# paper_tape.net
KiCad netlist of a schematic drawn in EAGLE
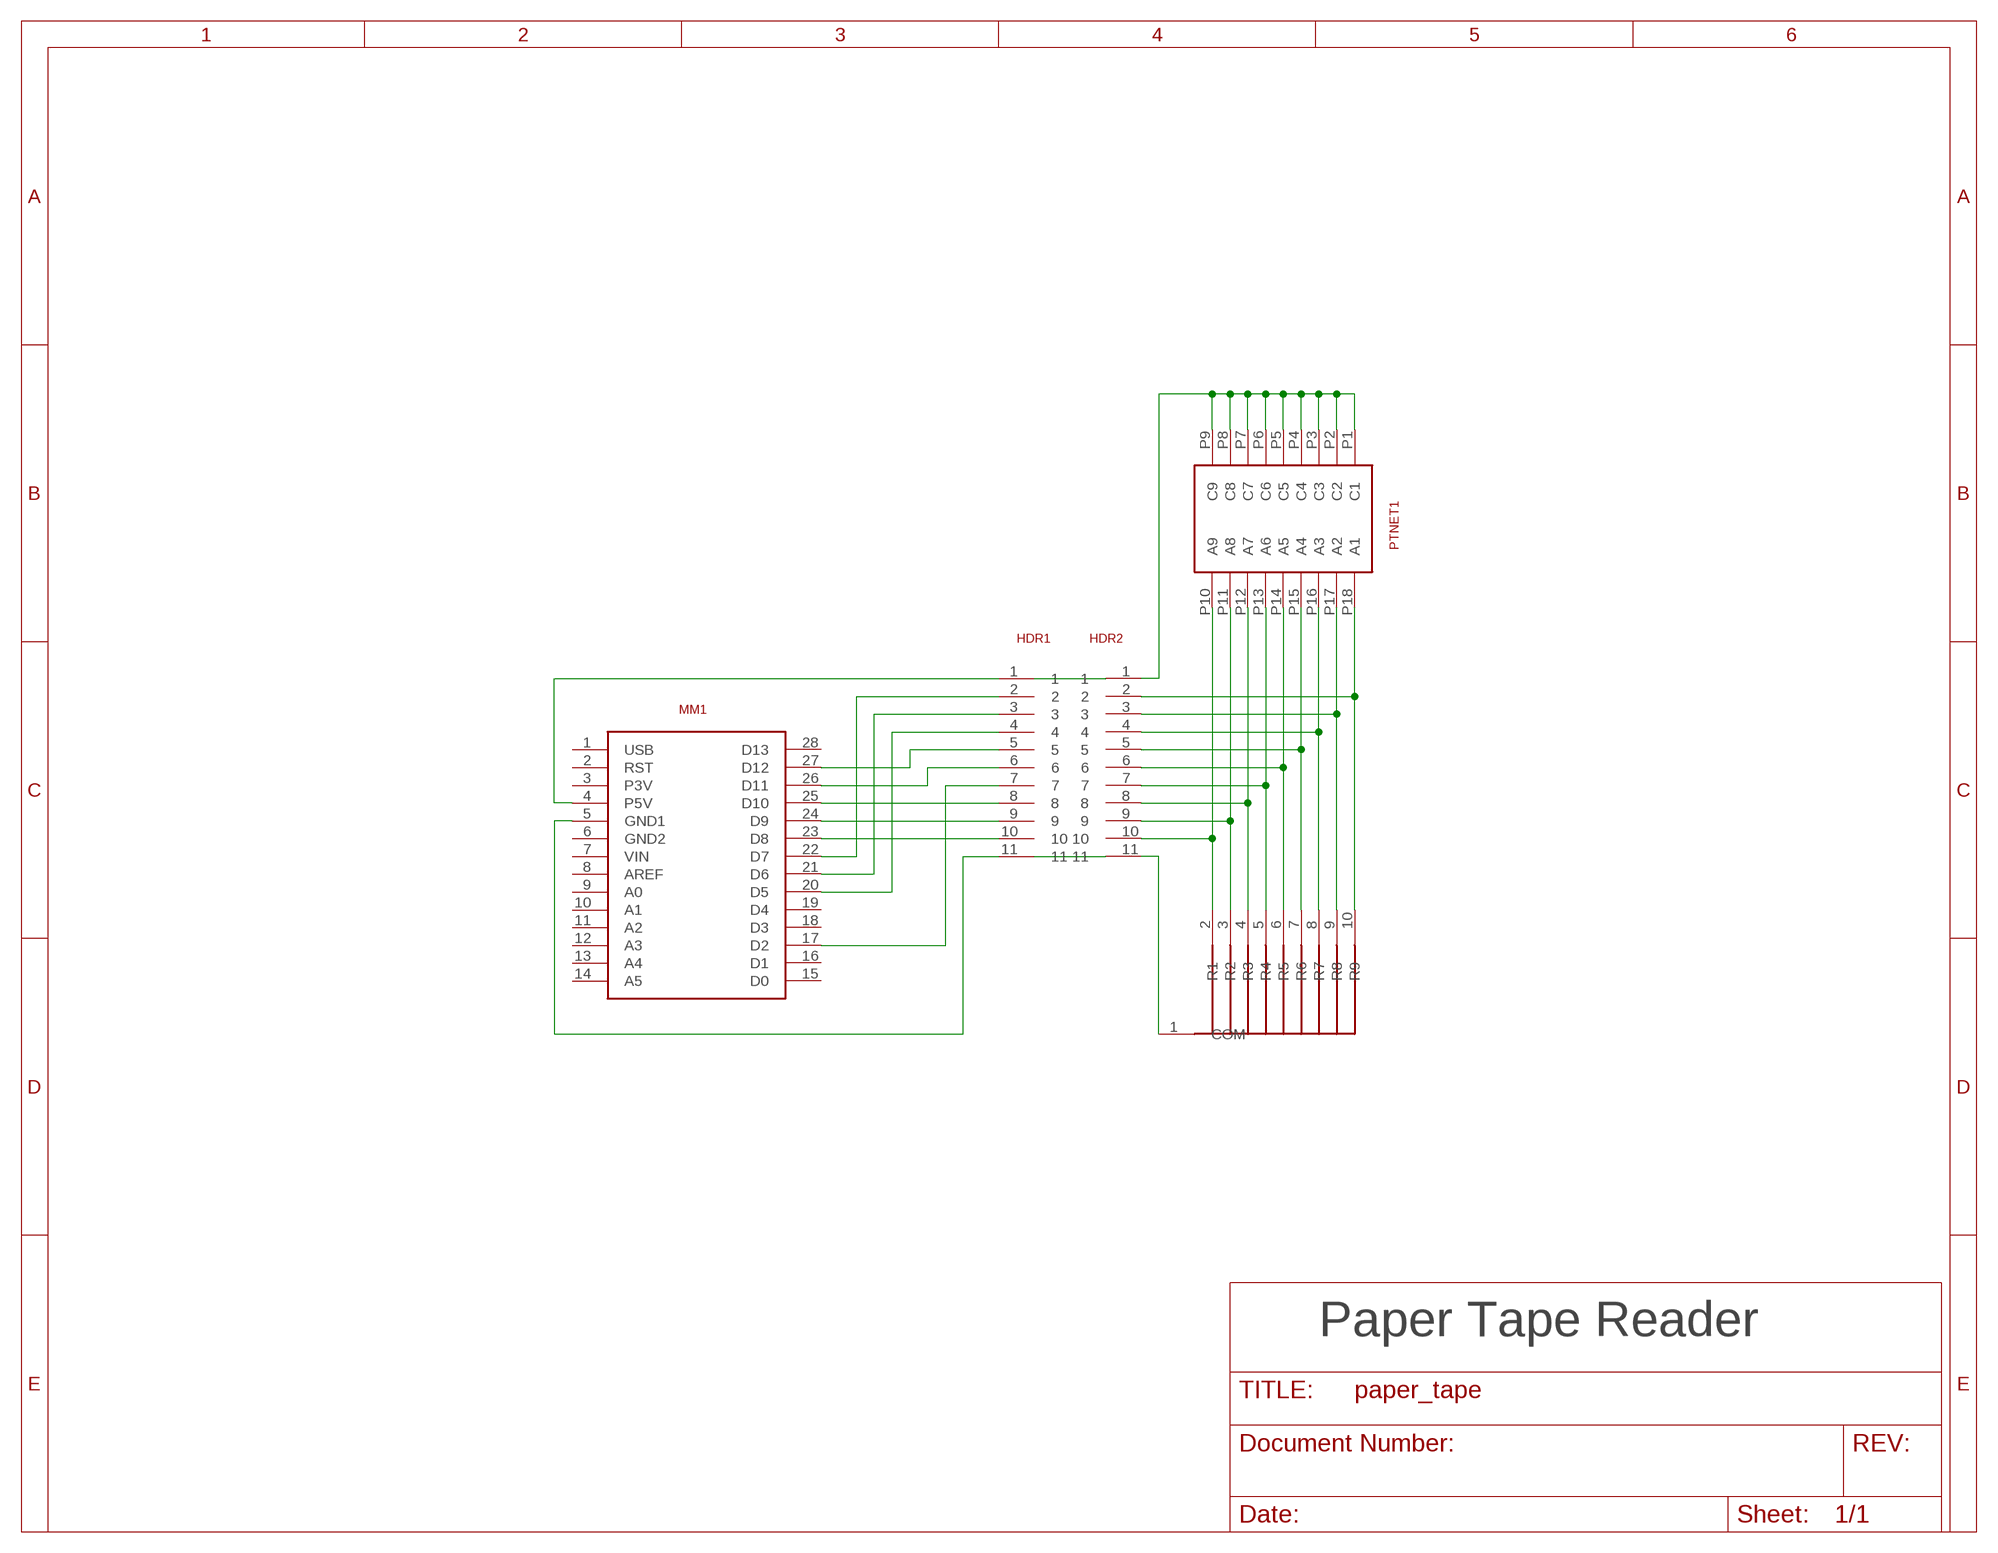
[diagram p0: schematic, sheet 1]

(export (version "E")
  (design (tool "Eeschema 10.0.6"))
  (components
    (comp (ref "HDR1")
      (value "HEADER")
      (footprint "eagle-import:SIP11")
      (libsource (lib "eagle-import") (part "HEADER"))
    )
    (comp (ref "HDR2")
      (value "HEADER")
      (footprint "eagle-import:SIP11")
      (libsource (lib "eagle-import") (part "HEADER"))
    )
    (comp (ref "MM1")
      (value "METRO_MINI")
      (footprint "eagle-import:DIP28")
      (libsource (lib "eagle-import") (part "METRO_MINI"))
    )
    (comp (ref "PTNET1")
      (value "PBX89")
      (footprint "eagle-import:DIP18N")
      (libsource (lib "eagle-import") (part "PBX89"))
    )
    (comp (ref "RN1")
      (value "1k")
      (footprint "eagle-import:SIP10")
      (libsource (lib "eagle-import") (part "RNET"))
    )
  )
  (nets
    (net (code "1") (name "/GND") (class "Default")
      (node (ref "HDR1") (pin "11") (pinfunction "11_11") (pintype "bidirectional"))
      (node (ref "HDR2") (pin "11") (pinfunction "11_11") (pintype "bidirectional"))
      (node (ref "MM1") (pin "5") (pinfunction "GND1_5") (pintype "bidirectional"))
      (node (ref "RN1") (pin "1") (pinfunction "COM_1") (pintype "bidirectional"))
    )
    (net (code "2") (name "/P5V") (class "Default")
      (node (ref "HDR2") (pin "1") (pinfunction "1_1") (pintype "bidirectional"))
      (node (ref "PTNET1") (pin "P1") (pinfunction "C1_P1") (pintype "bidirectional"))
      (node (ref "PTNET1") (pin "P2") (pinfunction "C2_P2") (pintype "bidirectional"))
      (node (ref "PTNET1") (pin "P3") (pinfunction "C3_P3") (pintype "bidirectional"))
      (node (ref "PTNET1") (pin "P4") (pinfunction "C4_P4") (pintype "bidirectional"))
      (node (ref "PTNET1") (pin "P5") (pinfunction "C5_P5") (pintype "bidirectional"))
      (node (ref "PTNET1") (pin "P6") (pinfunction "C6_P6") (pintype "bidirectional"))
      (node (ref "PTNET1") (pin "P7") (pinfunction "C7_P7") (pintype "bidirectional"))
      (node (ref "PTNET1") (pin "P8") (pinfunction "C8_P8") (pintype "bidirectional"))
      (node (ref "PTNET1") (pin "P9") (pinfunction "C9_P9") (pintype "bidirectional"))
    )
    (net (code "3") (name "Net-(MM1-D2)") (class "Default")
      (node (ref "HDR1") (pin "7") (pinfunction "7_7") (pintype "bidirectional"))
      (node (ref "MM1") (pin "17") (pinfunction "D2_17") (pintype "bidirectional"))
    )
    (net (code "4") (name "Net-(MM1-D5)") (class "Default")
      (node (ref "HDR1") (pin "4") (pinfunction "4_4") (pintype "bidirectional"))
      (node (ref "MM1") (pin "20") (pinfunction "D5_20") (pintype "bidirectional"))
    )
    (net (code "5") (name "Net-(MM1-D6)") (class "Default")
      (node (ref "HDR1") (pin "3") (pinfunction "3_3") (pintype "bidirectional"))
      (node (ref "MM1") (pin "21") (pinfunction "D6_21") (pintype "bidirectional"))
    )
    (net (code "6") (name "Net-(MM1-D7)") (class "Default")
      (node (ref "HDR1") (pin "2") (pinfunction "2_2") (pintype "bidirectional"))
      (node (ref "MM1") (pin "22") (pinfunction "D7_22") (pintype "bidirectional"))
    )
    (net (code "7") (name "Net-(MM1-D8)") (class "Default")
      (node (ref "HDR1") (pin "10") (pinfunction "10_10") (pintype "bidirectional"))
      (node (ref "MM1") (pin "23") (pinfunction "D8_23") (pintype "bidirectional"))
    )
    (net (code "8") (name "Net-(MM1-D9)") (class "Default")
      (node (ref "HDR1") (pin "9") (pinfunction "9_9") (pintype "bidirectional"))
      (node (ref "MM1") (pin "24") (pinfunction "D9_24") (pintype "bidirectional"))
    )
    (net (code "9") (name "Net-(MM1-D10)") (class "Default")
      (node (ref "HDR1") (pin "8") (pinfunction "8_8") (pintype "bidirectional"))
      (node (ref "MM1") (pin "25") (pinfunction "D10_25") (pintype "bidirectional"))
    )
    (net (code "10") (name "Net-(MM1-D11)") (class "Default")
      (node (ref "HDR1") (pin "6") (pinfunction "6_6") (pintype "bidirectional"))
      (node (ref "MM1") (pin "26") (pinfunction "D11_26") (pintype "bidirectional"))
    )
    (net (code "11") (name "Net-(MM1-D12)") (class "Default")
      (node (ref "HDR1") (pin "5") (pinfunction "5_5") (pintype "bidirectional"))
      (node (ref "MM1") (pin "27") (pinfunction "D12_27") (pintype "bidirectional"))
    )
    (net (code "12") (name "Net-(MM1-P5V)") (class "Default")
      (node (ref "HDR1") (pin "1") (pinfunction "1_1") (pintype "bidirectional"))
      (node (ref "MM1") (pin "4") (pinfunction "P5V_4") (pintype "bidirectional"))
    )
    (net (code "13") (name "Net-(PTNET1-A1)") (class "Default")
      (node (ref "HDR2") (pin "2") (pinfunction "2_2") (pintype "bidirectional"))
      (node (ref "PTNET1") (pin "P18") (pinfunction "A1_P18") (pintype "bidirectional"))
      (node (ref "RN1") (pin "10") (pinfunction "R9_10") (pintype "bidirectional"))
    )
    (net (code "14") (name "Net-(PTNET1-A2)") (class "Default")
      (node (ref "HDR2") (pin "3") (pinfunction "3_3") (pintype "bidirectional"))
      (node (ref "PTNET1") (pin "P17") (pinfunction "A2_P17") (pintype "bidirectional"))
      (node (ref "RN1") (pin "9") (pinfunction "R8_9") (pintype "bidirectional"))
    )
    (net (code "15") (name "Net-(PTNET1-A3)") (class "Default")
      (node (ref "HDR2") (pin "4") (pinfunction "4_4") (pintype "bidirectional"))
      (node (ref "PTNET1") (pin "P16") (pinfunction "A3_P16") (pintype "bidirectional"))
      (node (ref "RN1") (pin "8") (pinfunction "R7_8") (pintype "bidirectional"))
    )
    (net (code "16") (name "Net-(PTNET1-A4)") (class "Default")
      (node (ref "HDR2") (pin "5") (pinfunction "5_5") (pintype "bidirectional"))
      (node (ref "PTNET1") (pin "P15") (pinfunction "A4_P15") (pintype "bidirectional"))
      (node (ref "RN1") (pin "7") (pinfunction "R6_7") (pintype "bidirectional"))
    )
    (net (code "17") (name "Net-(PTNET1-A5)") (class "Default")
      (node (ref "HDR2") (pin "6") (pinfunction "6_6") (pintype "bidirectional"))
      (node (ref "PTNET1") (pin "P14") (pinfunction "A5_P14") (pintype "bidirectional"))
      (node (ref "RN1") (pin "6") (pinfunction "R5_6") (pintype "bidirectional"))
    )
    (net (code "18") (name "Net-(PTNET1-A6)") (class "Default")
      (node (ref "HDR2") (pin "7") (pinfunction "7_7") (pintype "bidirectional"))
      (node (ref "PTNET1") (pin "P13") (pinfunction "A6_P13") (pintype "bidirectional"))
      (node (ref "RN1") (pin "5") (pinfunction "R4_5") (pintype "bidirectional"))
    )
    (net (code "19") (name "Net-(PTNET1-A7)") (class "Default")
      (node (ref "HDR2") (pin "8") (pinfunction "8_8") (pintype "bidirectional"))
      (node (ref "PTNET1") (pin "P12") (pinfunction "A7_P12") (pintype "bidirectional"))
      (node (ref "RN1") (pin "4") (pinfunction "R3_4") (pintype "bidirectional"))
    )
    (net (code "20") (name "Net-(PTNET1-A8)") (class "Default")
      (node (ref "HDR2") (pin "9") (pinfunction "9_9") (pintype "bidirectional"))
      (node (ref "PTNET1") (pin "P11") (pinfunction "A8_P11") (pintype "bidirectional"))
      (node (ref "RN1") (pin "3") (pinfunction "R2_3") (pintype "bidirectional"))
    )
    (net (code "21") (name "Net-(PTNET1-A9)") (class "Default")
      (node (ref "HDR2") (pin "10") (pinfunction "10_10") (pintype "bidirectional"))
      (node (ref "PTNET1") (pin "P10") (pinfunction "A9_P10") (pintype "bidirectional"))
      (node (ref "RN1") (pin "2") (pinfunction "R1_2") (pintype "bidirectional"))
    )
    (net (code "22") (name "unconnected-(MM1-A0-Pad9)") (class "Default")
      (node (ref "MM1") (pin "9") (pinfunction "A0_9") (pintype "bidirectional"))
    )
    (net (code "23") (name "unconnected-(MM1-A1-Pad10)") (class "Default")
      (node (ref "MM1") (pin "10") (pinfunction "A1_10") (pintype "bidirectional"))
    )
    (net (code "24") (name "unconnected-(MM1-A2-Pad11)") (class "Default")
      (node (ref "MM1") (pin "11") (pinfunction "A2_11") (pintype "bidirectional"))
    )
    (net (code "25") (name "unconnected-(MM1-A3-Pad12)") (class "Default")
      (node (ref "MM1") (pin "12") (pinfunction "A3_12") (pintype "bidirectional"))
    )
    (net (code "26") (name "unconnected-(MM1-A4-Pad13)") (class "Default")
      (node (ref "MM1") (pin "13") (pinfunction "A4_13") (pintype "bidirectional"))
    )
    (net (code "27") (name "unconnected-(MM1-A5-Pad14)") (class "Default")
      (node (ref "MM1") (pin "14") (pinfunction "A5_14") (pintype "bidirectional"))
    )
    (net (code "28") (name "unconnected-(MM1-AREF-Pad8)") (class "Default")
      (node (ref "MM1") (pin "8") (pinfunction "AREF_8") (pintype "bidirectional"))
    )
    (net (code "29") (name "unconnected-(MM1-D0-Pad15)") (class "Default")
      (node (ref "MM1") (pin "15") (pinfunction "D0_15") (pintype "bidirectional"))
    )
    (net (code "30") (name "unconnected-(MM1-D1-Pad16)") (class "Default")
      (node (ref "MM1") (pin "16") (pinfunction "D1_16") (pintype "bidirectional"))
    )
    (net (code "31") (name "unconnected-(MM1-D3-Pad18)") (class "Default")
      (node (ref "MM1") (pin "18") (pinfunction "D3_18") (pintype "bidirectional"))
    )
    (net (code "32") (name "unconnected-(MM1-D4-Pad19)") (class "Default")
      (node (ref "MM1") (pin "19") (pinfunction "D4_19") (pintype "bidirectional"))
    )
    (net (code "33") (name "unconnected-(MM1-D13-Pad28)") (class "Default")
      (node (ref "MM1") (pin "28") (pinfunction "D13_28") (pintype "bidirectional"))
    )
    (net (code "34") (name "unconnected-(MM1-GND2-Pad6)") (class "Default")
      (node (ref "MM1") (pin "6") (pinfunction "GND2_6") (pintype "bidirectional"))
    )
    (net (code "35") (name "unconnected-(MM1-P3V-Pad3)") (class "Default")
      (node (ref "MM1") (pin "3") (pinfunction "P3V_3") (pintype "bidirectional"))
    )
    (net (code "36") (name "unconnected-(MM1-RST-Pad2)") (class "Default")
      (node (ref "MM1") (pin "2") (pinfunction "RST_2") (pintype "bidirectional"))
    )
    (net (code "37") (name "unconnected-(MM1-USB-Pad1)") (class "Default")
      (node (ref "MM1") (pin "1") (pinfunction "USB_1") (pintype "bidirectional"))
    )
    (net (code "38") (name "unconnected-(MM1-VIN-Pad7)") (class "Default")
      (node (ref "MM1") (pin "7") (pinfunction "VIN_7") (pintype "bidirectional"))
    )
  )
)
